# Major_Buzz_Kill.net
KiCad netlist of a schematic drawn in Altium Designer
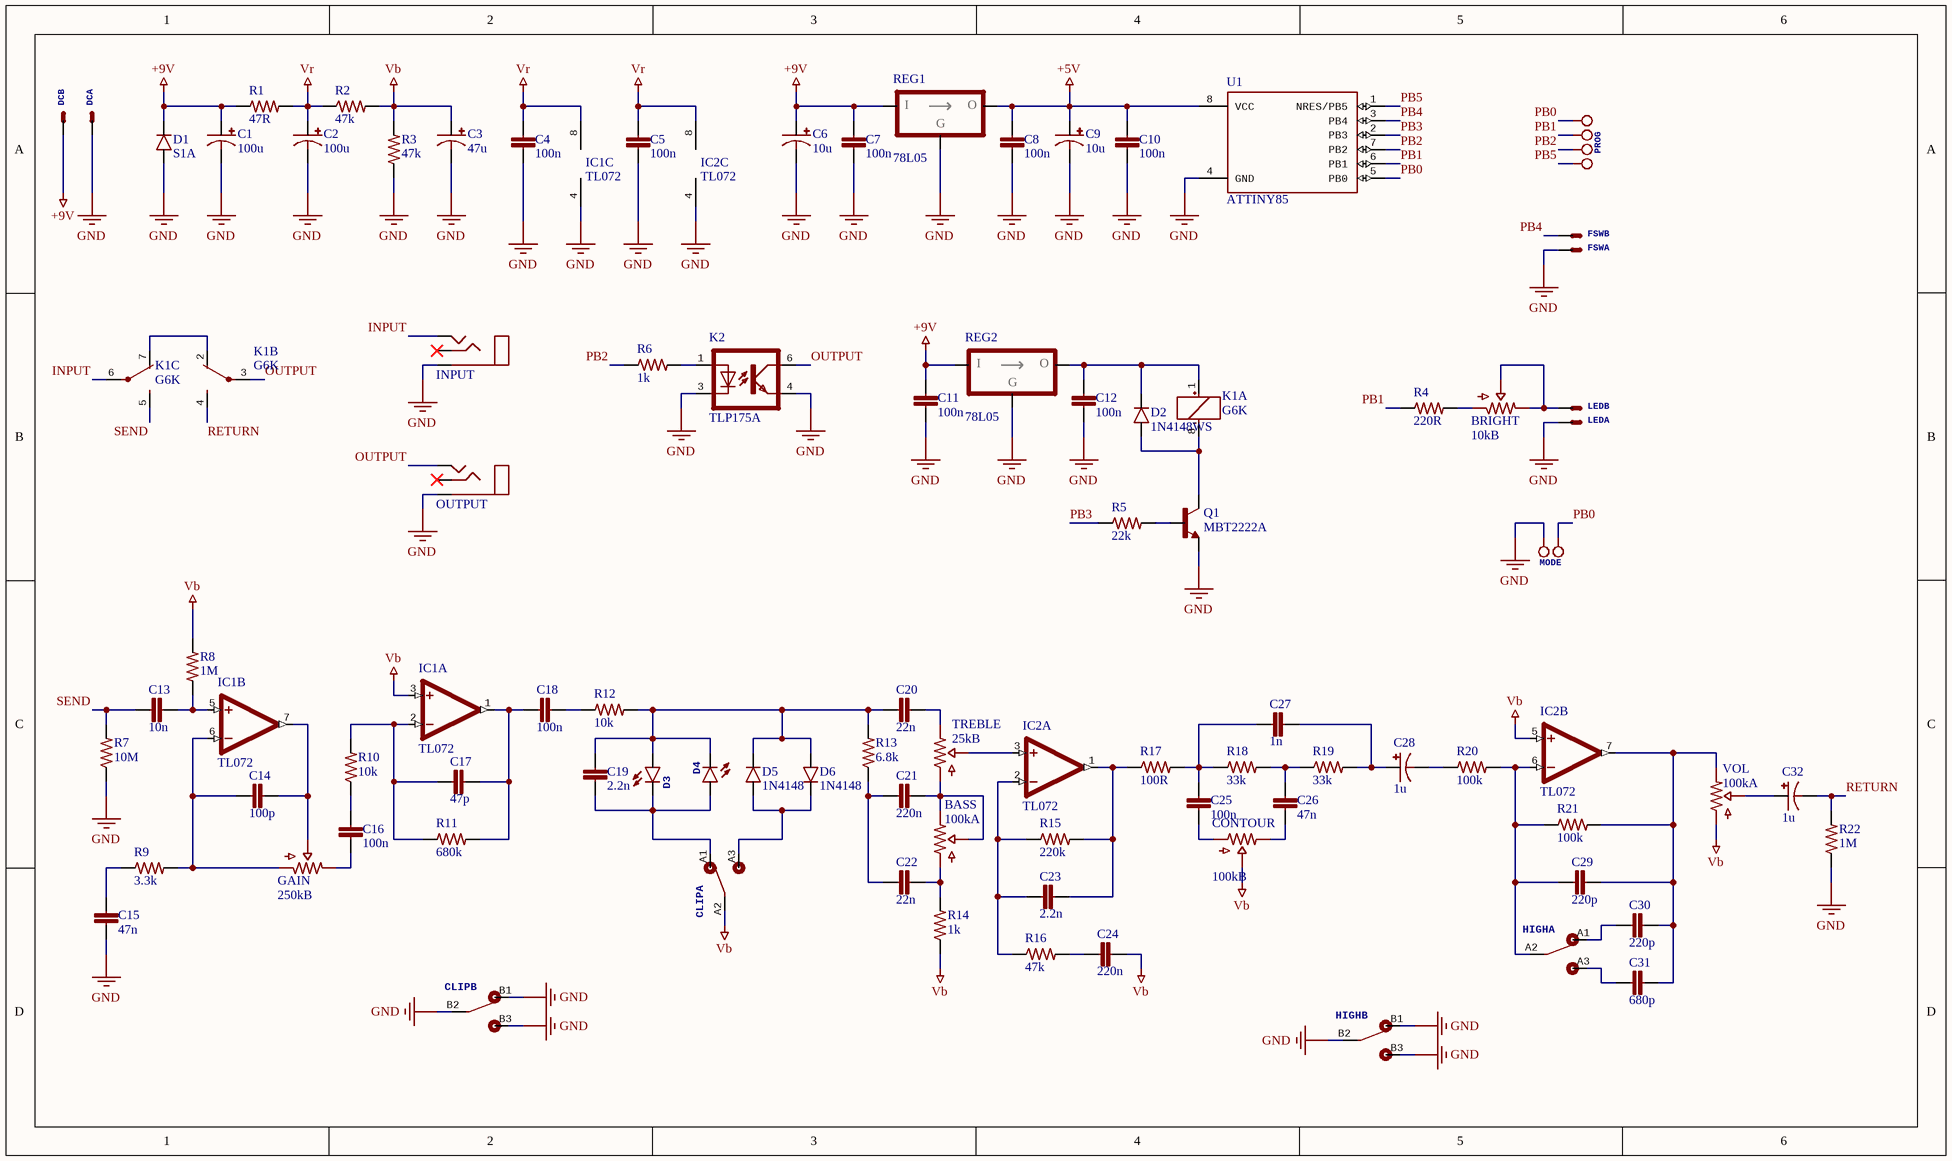
[diagram p0: Major Buzz Kill.SchDoc]

(export (version "E")
  (design (tool "Eeschema 10.0.6"))
  (components
    (comp (ref "BASS")
      (value "100kA")
      (footprint "ALPHA_16mm_BOTTOM")
      (description "100k Log potentiometer round shaft")
      (libsource (lib "Pedals") (part "POT_100kA_ALPHA_16mm"))
    )
    (comp (ref "BRIGHT")
      (value "10kB")
      (footprint "BOURNS_3362P")
      (description "10k Lin 3362P trimmer")
      (libsource (lib "Pedals") (part "TRIM_10kB_3362P"))
    )
    (comp (ref "C1")
      (value "100u")
      (footprint "CAPAE_D")
      (description "CAP ALUM 100UF 25V SMD")
      (fields
        (field (name "MANUFACTURER") "Multicomp")
        (field (name "MANUFACTURER PART NUMBER") "MCVVT025M101EA6L")
      )
      (libsource (lib "Pedals SMD") (part "MCVVT025M101EA6L"))
    )
    (comp (ref "C2")
      (value "100u")
      (footprint "CAPAE_D")
      (description "CAP ALUM 100UF 25V SMD")
      (fields
        (field (name "MANUFACTURER") "Multicomp")
        (field (name "MANUFACTURER PART NUMBER") "MCVVT025M101EA6L")
      )
      (libsource (lib "Pedals SMD") (part "MCVVT025M101EA6L"))
    )
    (comp (ref "C3")
      (value "47u")
      (footprint "CAPAE_D")
      (description "CAP ALUM 47UF 25V SMD")
      (fields
        (field (name "MANUFACTURER") "Multicomp")
        (field (name "MANUFACTURER PART NUMBER") "MCVVT025M470EA1L")
      )
      (libsource (lib "Pedals SMD") (part "MCVVT025M470EA1L"))
    )
    (comp (ref "C4")
      (value "100n")
      (footprint "CHIP_0603")
      (description "CAP CER 100NF 50V X7R 0603")
      (fields
        (field (name "MANUFACTURER") "Multicomp")
        (field (name "MANUFACTURER PART NUMBER") "MC0603B104K500CT")
      )
      (libsource (lib "Pedals SMD") (part "MC0603B104K500CT"))
    )
    (comp (ref "C5")
      (value "100n")
      (footprint "CHIP_0603")
      (description "CAP CER 100NF 50V X7R 0603")
      (fields
        (field (name "MANUFACTURER") "Multicomp")
        (field (name "MANUFACTURER PART NUMBER") "MC0603B104K500CT")
      )
      (libsource (lib "Pedals SMD") (part "MC0603B104K500CT"))
    )
    (comp (ref "C6")
      (value "10u")
      (footprint "CAPAE_B")
      (description "CAP ALUM 10UF 25V SMD")
      (fields
        (field (name "MANUFACTURER") "Multicomp")
        (field (name "MANUFACTURER PART NUMBER") "MCVVT025M100CA1L")
      )
      (libsource (lib "Pedals SMD") (part "MCVVT025M100CA1L"))
    )
    (comp (ref "C7")
      (value "100n")
      (footprint "CHIP_0603")
      (description "CAP CER 100NF 50V X7R 0603")
      (fields
        (field (name "MANUFACTURER") "Multicomp")
        (field (name "MANUFACTURER PART NUMBER") "MC0603B104K500CT")
      )
      (libsource (lib "Pedals SMD") (part "MC0603B104K500CT"))
    )
    (comp (ref "C8")
      (value "100n")
      (footprint "CHIP_0603")
      (description "CAP CER 100NF 50V X7R 0603")
      (fields
        (field (name "MANUFACTURER") "Multicomp")
        (field (name "MANUFACTURER PART NUMBER") "MC0603B104K500CT")
      )
      (libsource (lib "Pedals SMD") (part "MC0603B104K500CT"))
    )
    (comp (ref "C9")
      (value "10u")
      (footprint "CAPAE_B")
      (description "CAP ALUM 10UF 25V SMD")
      (fields
        (field (name "MANUFACTURER") "Multicomp")
        (field (name "MANUFACTURER PART NUMBER") "MCVVT025M100CA1L")
      )
      (libsource (lib "Pedals SMD") (part "MCVVT025M100CA1L"))
    )
    (comp (ref "C10")
      (value "100n")
      (footprint "CHIP_0603")
      (description "CAP CER 100NF 50V X7R 0603")
      (fields
        (field (name "MANUFACTURER") "Multicomp")
        (field (name "MANUFACTURER PART NUMBER") "MC0603B104K500CT")
      )
      (libsource (lib "Pedals SMD") (part "MC0603B104K500CT"))
    )
    (comp (ref "C11")
      (value "100n")
      (footprint "CHIP_0603")
      (description "CAP CER 100NF 50V X7R 0603")
      (fields
        (field (name "MANUFACTURER") "Multicomp")
        (field (name "MANUFACTURER PART NUMBER") "MC0603B104K500CT")
      )
      (libsource (lib "Pedals SMD") (part "MC0603B104K500CT"))
    )
    (comp (ref "C12")
      (value "100n")
      (footprint "CHIP_0603")
      (description "CAP CER 100NF 50V X7R 0603")
      (fields
        (field (name "MANUFACTURER") "Multicomp")
        (field (name "MANUFACTURER PART NUMBER") "MC0603B104K500CT")
      )
      (libsource (lib "Pedals SMD") (part "MC0603B104K500CT"))
    )
    (comp (ref "C13")
      (value "10n")
      (footprint "CHIP_0603")
      (description "CAP CER 10NF 50V C0G/NP0 0603")
      (fields
        (field (name "MANUFACTURER") "Murata")
        (field (name "MANUFACTURER PART NUMBER") "GRM1885C1H103JA01D")
      )
      (libsource (lib "Pedals SMD") (part "GRM1885C1H103JA01D"))
    )
    (comp (ref "C14")
      (value "100p")
      (footprint "CHIP_0603")
      (description "CAP CER 100PF 50V C0G/NP0 0603")
      (fields
        (field (name "MANUFACTURER") "Multicomp")
        (field (name "MANUFACTURER PART NUMBER") "MC0603N101J500CT")
      )
      (libsource (lib "Pedals SMD") (part "MC0603N101J500CT"))
    )
    (comp (ref "C15")
      (value "47n")
      (footprint "CHIP_0603")
      (description "CAP CER 47NF 50V X7R 0603")
      (fields
        (field (name "MANUFACTURER") "Multicomp")
        (field (name "MANUFACTURER PART NUMBER") "MC0603B473K500CT")
      )
      (libsource (lib "Pedals SMD") (part "MC0603B473K500CT"))
    )
    (comp (ref "C16")
      (value "100n")
      (footprint "CHIP_1206")
      (description "CAP CER 100NF 50V C0G/NP0 1206")
      (fields
        (field (name "MANUFACTURER") "Murata")
        (field (name "MANUFACTURER PART NUMBER") "GRM31C5C1H104JA01L")
      )
      (libsource (lib "Pedals SMD") (part "GRM31C5C1H104JA01L"))
    )
    (comp (ref "C17")
      (value "47p")
      (footprint "CHIP_0603")
      (description "CAP CER 47PF 50V C0G/NP0 0603")
      (fields
        (field (name "MANUFACTURER") "Multicomp")
        (field (name "MANUFACTURER PART NUMBER") "MC0603N470J500CT")
      )
      (libsource (lib "Pedals SMD") (part "MC0603N470J500CT"))
    )
    (comp (ref "C18")
      (value "100n")
      (footprint "CHIP_1206")
      (description "CAP CER 100NF 50V C0G/NP0 1206")
      (fields
        (field (name "MANUFACTURER") "Murata")
        (field (name "MANUFACTURER PART NUMBER") "GRM31C5C1H104JA01L")
      )
      (libsource (lib "") (part "GRM31C5C1H104JA01L_1"))
    )
    (comp (ref "C19")
      (value "2.2n")
      (footprint "CHIP_0603")
      (description "CAP CER 2.2NF 50V C0G/NP0 0603")
      (fields
        (field (name "MANUFACTURER") "Murata")
        (field (name "MANUFACTURER PART NUMBER") "GRM1885C1H222JA01D")
      )
      (libsource (lib "Pedals SMD") (part "GRM1885C1H222JA01D"))
    )
    (comp (ref "C20")
      (value "22n")
      (footprint "CHIP_0805")
      (description "CAP CER 22NF 50V C0G/NP0 0805")
      (fields
        (field (name "MANUFACTURER") "Murata")
        (field (name "MANUFACTURER PART NUMBER") "GRM21B5C1H223JA01L")
      )
      (libsource (lib "Pedals SMD") (part "GRM21B5C1H223JA01L"))
    )
    (comp (ref "C21")
      (value "220n")
      (footprint "CHIP_0603")
      (description "CAP CER 220n 50V X7R 0603")
      (fields
        (field (name "MANUFACTURER") "Murata")
        (field (name "MANUFACTURER PART NUMBER") "GCM188R71H224KA64D")
      )
      (libsource (lib "Pedals SMD") (part "GCM188R71H224KA64D"))
    )
    (comp (ref "C22")
      (value "22n")
      (footprint "CHIP_0805")
      (description "CAP CER 22NF 50V C0G/NP0 0805")
      (fields
        (field (name "MANUFACTURER") "Murata")
        (field (name "MANUFACTURER PART NUMBER") "GRM21B5C1H223JA01L")
      )
      (libsource (lib "Pedals SMD") (part "GRM21B5C1H223JA01L"))
    )
    (comp (ref "C23")
      (value "2.2n")
      (footprint "CHIP_0603")
      (description "CAP CER 2.2NF 50V C0G/NP0 0603")
      (fields
        (field (name "MANUFACTURER") "Murata")
        (field (name "MANUFACTURER PART NUMBER") "GRM1885C1H222JA01D")
      )
      (libsource (lib "") (part "GRM1885C1H222JA01D_1"))
    )
    (comp (ref "C24")
      (value "220n")
      (footprint "CHIP_0603")
      (description "CAP CER 220n 50V X7R 0603")
      (fields
        (field (name "MANUFACTURER") "Murata")
        (field (name "MANUFACTURER PART NUMBER") "GCM188R71H224KA64D")
      )
      (libsource (lib "Pedals SMD") (part "GCM188R71H224KA64D"))
    )
    (comp (ref "C25")
      (value "100n")
      (footprint "CHIP_1206")
      (description "CAP CER 100NF 50V C0G/NP0 1206")
      (fields
        (field (name "MANUFACTURER") "Murata")
        (field (name "MANUFACTURER PART NUMBER") "GRM31C5C1H104JA01L")
      )
      (libsource (lib "Pedals SMD") (part "GRM31C5C1H104JA01L"))
    )
    (comp (ref "C26")
      (value "47n")
      (footprint "CHIP_1206")
      (description "CAP CER 47NF 50V C0G/NP0 1206")
      (fields
        (field (name "MANUFACTURER") "Murata")
        (field (name "MANUFACTURER PART NUMBER") "GCM31M5C1H473JA16L")
      )
      (libsource (lib "Pedals SMD") (part "GCM31M5C1H473JA16L"))
    )
    (comp (ref "C27")
      (value "1n")
      (footprint "CHIP_0603")
      (description "CAP CER 1NF 50V C0G/NP0 0603")
      (fields
        (field (name "MANUFACTURER") "Murata")
        (field (name "MANUFACTURER PART NUMBER") "GRM1885C1H102JA01D")
      )
      (libsource (lib "Pedals SMD") (part "GRM1885C1H102JA01D"))
    )
    (comp (ref "C28")
      (value "1u")
      (footprint "CAPAE_B")
      (description "CAP ALUM 1UF 50V LESR SMD")
      (fields
        (field (name "MANUFACTURER") "Panasonic")
        (field (name "MANUFACTURER PART NUMBER") "EEEFC1H1R0R")
      )
      (libsource (lib "Pedals SMD") (part "EEEFC1H1R0R"))
    )
    (comp (ref "C29")
      (value "220p")
      (footprint "CHIP_0603")
      (description "CAP CER 220PF 50V C0G/NP0 0603")
      (fields
        (field (name "MANUFACTURER") "Multicomp")
        (field (name "MANUFACTURER PART NUMBER") "MC0603N221J500CT")
      )
      (libsource (lib "Pedals SMD") (part "MC0603N221J500CT"))
    )
    (comp (ref "C30")
      (value "220p")
      (footprint "CHIP_0603")
      (description "CAP CER 220PF 50V C0G/NP0 0603")
      (fields
        (field (name "MANUFACTURER") "Multicomp")
        (field (name "MANUFACTURER PART NUMBER") "MC0603N221J500CT")
      )
      (libsource (lib "Pedals SMD") (part "MC0603N221J500CT"))
    )
    (comp (ref "C31")
      (value "680p")
      (footprint "CHIP_0603")
      (description "CAP CER 680PF 50V C0G/NP0 0603")
      (fields
        (field (name "MANUFACTURER") "Multicomp")
        (field (name "MANUFACTURER PART NUMBER") "MC0603N681J500CT")
      )
      (libsource (lib "Pedals SMD") (part "MC0603N681J500CT"))
    )
    (comp (ref "C32")
      (value "1u")
      (footprint "CAPAE_B")
      (description "CAP ALUM 1UF 50V LESR SMD")
      (fields
        (field (name "MANUFACTURER") "Panasonic")
        (field (name "MANUFACTURER PART NUMBER") "EEEFC1H1R0R")
      )
      (libsource (lib "Pedals SMD") (part "EEEFC1H1R0R"))
    )
    (comp (ref "CLIP")
      (value "DPDT")
      (footprint "DPDT_SLIDE")
      (description "DPDT slide switch ON/OFF/ON")
      (libsource (lib "") (part "SW_SLIDE_DPDT_ON-OFF-ON_1"))
    )
    (comp (ref "CONTOUR")
      (value "100kB")
      (footprint "ALPHA_16mm_BOTTOM")
      (description "100k Lin potentiometer round shaft")
      (libsource (lib "Pedals") (part "POT_100kB_ALPHA_16mm"))
    )
    (comp (ref "D1")
      (value "S1A")
      (footprint "DO214")
      (description "DIODE GEN PURP 50V 1A SMA")
      (fields (field (name "MANUFACTURER") "ON Semiconductor / Fairchild"))
      (libsource (lib "Pedals SMD") (part "S1A"))
    )
    (comp (ref "D2")
      (value "1N4148WS")
      (footprint "SOD323")
      (description "DIODE GEN PURP 75V 150MA SOD323F")
      (fields (field (name "MANUFACTURER") "ON Semiconductor / Fairchild"))
      (libsource (lib "Pedals SMD") (part "1N4148WS"))
    )
    (comp (ref "D3")
      (value "D_LED")
      (footprint "LED_3MM")
      (description "LED")
      (libsource (lib "Pedals") (part "D_LED"))
    )
    (comp (ref "D4")
      (value "D_LED")
      (footprint "LED_3MM")
      (description "LED")
      (libsource (lib "Pedals") (part "D_LED"))
    )
    (comp (ref "D5") (value "1N4148") (footprint "DO35_2") (libsource (lib "Pedals") (part "D_1N4148")))
    (comp (ref "D6") (value "1N4148") (footprint "DO35_2") (libsource (lib "Pedals") (part "D_1N4148")))
    (comp (ref "DC")
      (value "J_JST-XH-02")
      (footprint "JST-XH-02")
      (description "2 Pins male XH header")
      (libsource (lib "Pedals") (part "J_JST-XH-02"))
    )
    (comp (ref "FSW")
      (value "J_JST-XH-02")
      (footprint "JST-XH-02")
      (description "2 Pins male XH header")
      (libsource (lib "Pedals") (part "J_JST-XH-02"))
    )
    (comp (ref "GAIN")
      (value "250kB")
      (footprint "ALPHA_16mm_BOTTOM")
      (description "250k Lin potentiometer round shaft")
      (libsource (lib "Pedals") (part "POT_250kB_ALPHA_16mm"))
    )
    (comp (ref "HIGH")
      (value "DPDT")
      (footprint "DPDT_SLIDE")
      (description "DPDT slide switch ON/OFF/ON")
      (libsource (lib "") (part "SW_SLIDE_DPDT_ON-OFF-ON_2"))
    )
    (comp (ref "IC1")
      (value "TL072")
      (footprint "SO-8")
      (description "IC OPAMP JFET 4MHZ 8SO")
      (fields
        (field (name "MANUFACTURER") "STMicroelectronics")
        (field (name "MANUFACTURER PART NUMBER") "TL072CDT")
      )
      (libsource (lib "Pedals SMD") (part "TL072CDT"))
    )
    (comp (ref "IC2")
      (value "TL072")
      (footprint "SO-8")
      (description "IC OPAMP JFET 4MHZ 8SO")
      (fields
        (field (name "MANUFACTURER") "STMicroelectronics")
        (field (name "MANUFACTURER PART NUMBER") "TL072CDT")
      )
      (libsource (lib "Pedals SMD") (part "TL072CDT"))
    )
    (comp (ref "INPUT")
      (value "J_STEREO")
      (footprint "STEREO")
      (description "6.35mm stereo insulated socket jack PCB mounted")
      (libsource (lib "Pedals") (part "J_STEREO"))
    )
    (comp (ref "K1")
      (value "G6K")
      (footprint "G6K")
      (description "OMRON - G6K-2F 5DC - RELAY, SIGNAL, DPDT, 30VDC, 1A")
      (fields (field (name "MANUFACTURER") "Cliff") (field (name "MANUFACTURER PART NUMBER") "G6K-2F5DC"))
      (libsource (lib "") (part "G6K-2F5DC_1"))
    )
    (comp (ref "K2")
      (value "TLP175A")
      (footprint "TLP175A")
      (description "Toshiba TLP175A AC Input MOSFET Output Optocoupler, Surface Mount, 4-Pin SOIC")
      (fields (field (name "MANUFACTURER") "Toshiba"))
      (libsource (lib "Pedals SMD") (part "TLP175A"))
    )
    (comp (ref "LED")
      (value "J_JST-XH-02")
      (footprint "JST-XH-02")
      (description "2 Pins male XH header")
      (libsource (lib "Pedals") (part "J_JST-XH-02"))
    )
    (comp (ref "MODE")
      (value "J_HEADER_2PINS")
      (footprint "HEADER_2PINS")
      (description "2 Pins male header")
      (libsource (lib "Pedals") (part "J_HEADER_2PINS"))
    )
    (comp (ref "OUTPUT")
      (value "J_STEREO")
      (footprint "STEREO")
      (description "6.35mm stereo insulated socket jack PCB mounted")
      (libsource (lib "Pedals") (part "J_STEREO"))
    )
    (comp (ref "PROG")
      (value "J_HEADER_4PINS_FEM")
      (footprint "HEADER_4Pins_FEM")
      (description "4 Pins female header")
      (libsource (lib "Pedals") (part "J_HEADER_4PINS_FEM"))
    )
    (comp (ref "Q1")
      (value "MBT2222A")
      (footprint "SOT323")
      (description "TRANS NPN 40V 0.6A SOT323")
      (fields
        (field (name "MANUFACTURER") "ON Semiconductor")
        (field (name "MANUFACTURER PART NUMBER") "MMBT2222AWT1G")
      )
      (libsource (lib "Pedals SMD") (part "MMBT2222AWT1G"))
    )
    (comp (ref "R1")
      (value "47R")
      (footprint "CHIP_R_1206")
      (description "RES SMD 47 OHM 1% 1/4W 1206")
      (fields
        (field (name "MANUFACTURER") "Vishay")
        (field (name "MANUFACTURER PART NUMBER") "CRCW120647R0FKEA")
      )
      (libsource (lib "Pedals SMD") (part "CRCW120647R0FKEA"))
    )
    (comp (ref "R2")
      (value "47k")
      (footprint "CHIP_R_1206")
      (description "RES SMD 47K OHM 1% 1/4W 1206")
      (fields
        (field (name "MANUFACTURER") "Vishay")
        (field (name "MANUFACTURER PART NUMBER") "CRCW120647K0FKEA")
      )
      (libsource (lib "Pedals SMD") (part "CRCW120647K0FKEA"))
    )
    (comp (ref "R3")
      (value "47k")
      (footprint "CHIP_R_1206")
      (description "RES SMD 47K OHM 1% 1/4W 1206")
      (fields
        (field (name "MANUFACTURER") "Vishay")
        (field (name "MANUFACTURER PART NUMBER") "CRCW120647K0FKEA")
      )
      (libsource (lib "Pedals SMD") (part "CRCW120647K0FKEA"))
    )
    (comp (ref "R4")
      (value "220R")
      (footprint "CHIP_R_1206")
      (description "RES SMD 220 OHM 1% 1/4W 1206")
      (fields
        (field (name "MANUFACTURER") "Vishay")
        (field (name "MANUFACTURER PART NUMBER") "CRCW1206220RFKEA")
      )
      (libsource (lib "Pedals SMD") (part "CRCW1206220RFKEA"))
    )
    (comp (ref "R5")
      (value "22k")
      (footprint "CHIP_R_0603")
      (description "RES SMD 22K OHM 1% 1/10W 0603")
      (fields
        (field (name "MANUFACTURER") "Vishay")
        (field (name "MANUFACTURER PART NUMBER") "CRCW060322K0FKEA")
      )
      (libsource (lib "Pedals SMD") (part "CRCW060322K0FKEA"))
    )
    (comp (ref "R6")
      (value "1k")
      (footprint "CHIP_R_0603")
      (description "RES SMD 1K OHM 1% 1/10W 0603")
      (fields
        (field (name "MANUFACTURER") "Vishay Dale")
        (field (name "MANUFACTURER PART NUMBER") "CRCW06031K00FKEA")
      )
      (libsource (lib "Pedals SMD") (part "CRCW06031K00FKEA"))
    )
    (comp (ref "R7")
      (value "10M")
      (footprint "CHIP_R_0603")
      (description "RES SMD 10M OHM 1% 1/10W 0603")
      (fields
        (field (name "MANUFACTURER") "Vishay")
        (field (name "MANUFACTURER PART NUMBER") "CRCW060310M0FKEA")
      )
      (libsource (lib "Pedals SMD") (part "CRCW060310M0FKEA"))
    )
    (comp (ref "R8")
      (value "1M")
      (footprint "CHIP_R_0603")
      (description "RES SMD 1M OHM 1% 1/10W 0603")
      (fields
        (field (name "MANUFACTURER") "Vishay")
        (field (name "MANUFACTURER PART NUMBER") "CRCW06031M00FKEA")
      )
      (libsource (lib "Pedals SMD") (part "CRCW06031M00FKEA"))
    )
    (comp (ref "R9")
      (value "3.3k")
      (footprint "CHIP_R_0603")
      (description "RES SMD 3.3K OHM 1% 1/10W 0603")
      (fields
        (field (name "MANUFACTURER") "Vishay")
        (field (name "MANUFACTURER PART NUMBER") "CRCW06033K30FKEA")
      )
      (libsource (lib "Pedals SMD") (part "CRCW06033K30FKEA"))
    )
    (comp (ref "R10")
      (value "10k")
      (footprint "CHIP_R_0603")
      (description "RES SMD 10K OHM 1% 1/10W 0603")
      (fields
        (field (name "MANUFACTURER") "Vishay")
        (field (name "MANUFACTURER PART NUMBER") "CRCW060310K0FKEA")
      )
      (libsource (lib "Pedals SMD") (part "CRCW060310K0FKEA"))
    )
    (comp (ref "R11")
      (value "680k")
      (footprint "CHIP_R_0603")
      (description "RES SMD 680K OHM 1% 1/10W 0603")
      (fields
        (field (name "MANUFACTURER") "Vishay")
        (field (name "MANUFACTURER PART NUMBER") "CRCW0603680KFKEA")
      )
      (libsource (lib "Pedals SMD") (part "CRCW0603680KFKEA"))
    )
    (comp (ref "R12")
      (value "10k")
      (footprint "CHIP_R_0603")
      (description "RES SMD 10K OHM 1% 1/10W 0603")
      (fields
        (field (name "MANUFACTURER") "Vishay")
        (field (name "MANUFACTURER PART NUMBER") "CRCW060310K0FKEA")
      )
      (libsource (lib "Pedals SMD") (part "CRCW060310K0FKEA"))
    )
    (comp (ref "R13")
      (value "6.8k")
      (footprint "CHIP_R_0603")
      (description "RES SMD 6.8K OHM 1% 1/10W 0603")
      (fields
        (field (name "MANUFACTURER") "Vishay")
        (field (name "MANUFACTURER PART NUMBER") "CRCW06036K80FKEA")
      )
      (libsource (lib "Pedals SMD") (part "CRCW06036K80FKEA"))
    )
    (comp (ref "R14")
      (value "1k")
      (footprint "CHIP_R_0603")
      (description "RES SMD 1K OHM 1% 1/10W 0603")
      (fields
        (field (name "MANUFACTURER") "Vishay Dale")
        (field (name "MANUFACTURER PART NUMBER") "CRCW06031K00FKEA")
      )
      (libsource (lib "Pedals SMD") (part "CRCW06031K00FKEA"))
    )
    (comp (ref "R15")
      (value "220k")
      (footprint "CHIP_R_0603")
      (description "RES SMD 220K OHM 1% 1/10W 0603")
      (fields
        (field (name "MANUFACTURER") "Vishay")
        (field (name "MANUFACTURER PART NUMBER") "CRCW0603220KFKEA")
      )
      (libsource (lib "Pedals SMD") (part "CRCW0603220KFKEA"))
    )
    (comp (ref "R16")
      (value "47k")
      (footprint "CHIP_R_0603")
      (description "RES SMD 47K OHM 1% 1/10W 0603")
      (fields
        (field (name "MANUFACTURER") "Vishay")
        (field (name "MANUFACTURER PART NUMBER") "CRCW060347K0FKEA")
      )
      (libsource (lib "Pedals SMD") (part "CRCW060347K0FKEA"))
    )
    (comp (ref "R17")
      (value "100R")
      (footprint "CHIP_R_0603")
      (description "RES SMD 100 OHM 1% 1/10W 0603")
      (fields
        (field (name "MANUFACTURER") "Vishay Dale")
        (field (name "MANUFACTURER PART NUMBER") "CRCW0603100RFKEA")
      )
      (libsource (lib "Pedals SMD") (part "CRCW0603100RFKEA"))
    )
    (comp (ref "R18")
      (value "33k")
      (footprint "CHIP_R_0603")
      (description "RES SMD 33K OHM 1% 1/10W 0603")
      (fields
        (field (name "MANUFACTURER") "Vishay")
        (field (name "MANUFACTURER PART NUMBER") "CRCW060333K0FKEA")
      )
      (libsource (lib "Pedals SMD") (part "CRCW060333K0FKEA"))
    )
    (comp (ref "R19")
      (value "33k")
      (footprint "CHIP_R_0603")
      (description "RES SMD 33K OHM 1% 1/10W 0603")
      (fields
        (field (name "MANUFACTURER") "Vishay")
        (field (name "MANUFACTURER PART NUMBER") "CRCW060333K0FKEA")
      )
      (libsource (lib "Pedals SMD") (part "CRCW060333K0FKEA"))
    )
    (comp (ref "R20")
      (value "100k")
      (footprint "CHIP_R_0603")
      (description "RES SMD 100K OHM 1% 1/10W 0603")
      (fields
        (field (name "MANUFACTURER") "Vishay")
        (field (name "MANUFACTURER PART NUMBER") "CRCW0603100KFKEA")
      )
      (libsource (lib "Pedals SMD") (part "CRCW0603100KFKEA"))
    )
    (comp (ref "R21")
      (value "100k")
      (footprint "CHIP_R_0603")
      (description "RES SMD 100K OHM 1% 1/10W 0603")
      (fields
        (field (name "MANUFACTURER") "Vishay")
        (field (name "MANUFACTURER PART NUMBER") "CRCW0603100KFKEA")
      )
      (libsource (lib "Pedals SMD") (part "CRCW0603100KFKEA"))
    )
    (comp (ref "R22")
      (value "1M")
      (footprint "CHIP_R_0603")
      (description "RES SMD 1M OHM 1% 1/10W 0603")
      (fields
        (field (name "MANUFACTURER") "Vishay")
        (field (name "MANUFACTURER PART NUMBER") "CRCW06031M00FKEA")
      )
      (libsource (lib "Pedals SMD") (part "CRCW06031M00FKEA"))
    )
    (comp (ref "REG1")
      (value "78L05")
      (footprint "SOT23-3")
      (description "TAIWAN SEMICONDUCTOR - TS78L05CX RFG - REG 3-TERMINAL 100MA, SMD, SOT23-3")
      (fields
        (field (name "MANUFACTURER") "Taiwan Semiconductor")
        (field (name "MANUFACTURER PART NUMBER") "TS78L05CXRFG")
      )
      (libsource (lib "Pedals SMD") (part "TS78L05CXRFG"))
    )
    (comp (ref "REG2")
      (value "78L05")
      (footprint "SOT23-3")
      (description "TAIWAN SEMICONDUCTOR - TS78L05CX RFG - REG 3-TERMINAL 100MA, SMD, SOT23-3")
      (fields
        (field (name "MANUFACTURER") "Taiwan Semiconductor")
        (field (name "MANUFACTURER PART NUMBER") "TS78L05CXRFG")
      )
      (libsource (lib "Pedals SMD") (part "TS78L05CXRFG"))
    )
    (comp (ref "TREBLE")
      (value "25kB")
      (footprint "ALPHA_16mm_BOTTOM")
      (description "25k Lin potentiometer round shaft")
      (libsource (lib "Pedals") (part "POT_25kB_ALPHA_16mm"))
    )
    (comp (ref "U1")
      (value "ATTINY85")
      (footprint "SOP8")
      (description "IC, 8BIT MCU, AVR TINY, 20MHZ, 8-SOIC")
      (fields
        (field (name "MANUFACTURER") "Microchip / Atmel")
        (field (name "MANUFACTURER PART NUMBER") "ATTINY85-20SU")
      )
      (libsource (lib "Pedals SMD") (part "ATTINY85-20SU"))
    )
    (comp (ref "VOL")
      (value "100kA")
      (footprint "ALPHA_16mm_BOTTOM")
      (description "100k Log potentiometer round shaft")
      (libsource (lib "Pedals") (part "POT_100kA_ALPHA_16mm"))
    )
  )
  (nets
    (net (code "1") (name "+5V") (class "Default")
      (node (ref "C10") (pin "1") (pinfunction "1_1") (pintype "passive"))
      (node (ref "C8") (pin "1") (pinfunction "1_1") (pintype "passive"))
      (node (ref "C9") (pin "+") (pinfunction "+_+") (pintype "passive"))
      (node (ref "REG1") (pin "1") (pinfunction "OUTPUT_1") (pintype "power_in"))
      (node (ref "U1") (pin "8") (pinfunction "VCC_8") (pintype "power_in"))
    )
    (net (code "2") (name "+9V") (class "Default")
      (node (ref "C1") (pin "+") (pinfunction "+_+") (pintype "passive"))
      (node (ref "C11") (pin "1") (pinfunction "1_1") (pintype "passive"))
      (node (ref "C6") (pin "+") (pinfunction "+_+") (pintype "passive"))
      (node (ref "C7") (pin "1") (pinfunction "1_1") (pintype "passive"))
      (node (ref "D1") (pin "1") (pinfunction "1_1") (pintype "passive"))
      (node (ref "DC") (pin "1") (pinfunction "S_1") (pintype "passive"))
      (node (ref "R1") (pin "1") (pinfunction "1_1") (pintype "passive"))
      (node (ref "REG1") (pin "2") (pinfunction "INPUT_2") (pintype "power_in"))
      (node (ref "REG2") (pin "2") (pinfunction "INPUT_2") (pintype "power_in"))
    )
    (net (code "3") (name "/INPUT") (class "Default")
      (node (ref "INPUT") (pin "T") (pinfunction "T_T") (pintype "passive"))
      (node (ref "K1") (pin "6") (pinfunction "P_6") (pintype "passive"))
    )
    (net (code "4") (name "/OUTPUT") (class "Default")
      (node (ref "K1") (pin "3") (pinfunction "P_3") (pintype "passive"))
      (node (ref "K2") (pin "6") (pinfunction "COL_6") (pintype "passive"))
      (node (ref "OUTPUT") (pin "T") (pinfunction "T_T") (pintype "passive"))
    )
    (net (code "5") (name "/PB0") (class "Default")
      (node (ref "MODE") (pin "2") (pinfunction "2_2") (pintype "passive"))
      (node (ref "PROG") (pin "4") (pinfunction "4_4") (pintype "passive"))
      (node (ref "U1") (pin "5") (pinfunction "PB0_5") (pintype "bidirectional"))
    )
    (net (code "6") (name "/PB1") (class "Default")
      (node (ref "PROG") (pin "3") (pinfunction "3_3") (pintype "passive"))
      (node (ref "R4") (pin "1") (pinfunction "1_1") (pintype "passive"))
      (node (ref "U1") (pin "6") (pinfunction "PB1_6") (pintype "bidirectional"))
    )
    (net (code "7") (name "/PB2") (class "Default")
      (node (ref "PROG") (pin "2") (pinfunction "2_2") (pintype "passive"))
      (node (ref "R6") (pin "1") (pinfunction "1_1") (pintype "passive"))
      (node (ref "U1") (pin "7") (pinfunction "PB2_7") (pintype "bidirectional"))
    )
    (net (code "8") (name "/PB3") (class "Default")
      (node (ref "R5") (pin "1") (pinfunction "1_1") (pintype "passive"))
      (node (ref "U1") (pin "2") (pinfunction "PB3_2") (pintype "bidirectional"))
    )
    (net (code "9") (name "/PB4") (class "Default")
      (node (ref "FSW") (pin "1") (pinfunction "S_1") (pintype "passive"))
      (node (ref "U1") (pin "3") (pinfunction "PB4_3") (pintype "bidirectional"))
    )
    (net (code "10") (name "/PB5") (class "Default")
      (node (ref "PROG") (pin "1") (pinfunction "1_1") (pintype "passive"))
      (node (ref "U1") (pin "1") (pinfunction "NRES/PB5_1") (pintype "bidirectional"))
    )
    (net (code "11") (name "/RETURN") (class "Default")
      (node (ref "C32") (pin "-") (pinfunction "-_-") (pintype "passive"))
      (node (ref "K1") (pin "4") (pinfunction "S_4") (pintype "passive"))
      (node (ref "R22") (pin "2") (pinfunction "2_2") (pintype "passive"))
    )
    (net (code "12") (name "/SEND") (class "Default")
      (node (ref "C13") (pin "2") (pinfunction "2_2") (pintype "passive"))
      (node (ref "K1") (pin "5") (pinfunction "S_5") (pintype "passive"))
      (node (ref "R7") (pin "2") (pinfunction "2_2") (pintype "passive"))
    )
    (net (code "13") (name "GND") (class "Default")
      (node (ref "C1") (pin "-") (pinfunction "-_-") (pintype "passive"))
      (node (ref "C10") (pin "2") (pinfunction "2_2") (pintype "passive"))
      (node (ref "C11") (pin "2") (pinfunction "2_2") (pintype "passive"))
      (node (ref "C12") (pin "2") (pinfunction "2_2") (pintype "passive"))
      (node (ref "C15") (pin "2") (pinfunction "2_2") (pintype "passive"))
      (node (ref "C2") (pin "-") (pinfunction "-_-") (pintype "passive"))
      (node (ref "C3") (pin "-") (pinfunction "-_-") (pintype "passive"))
      (node (ref "C4") (pin "2") (pinfunction "2_2") (pintype "passive"))
      (node (ref "C5") (pin "2") (pinfunction "2_2") (pintype "passive"))
      (node (ref "C6") (pin "-") (pinfunction "-_-") (pintype "passive"))
      (node (ref "C7") (pin "2") (pinfunction "2_2") (pintype "passive"))
      (node (ref "C8") (pin "2") (pinfunction "2_2") (pintype "passive"))
      (node (ref "C9") (pin "-") (pinfunction "-_-") (pintype "passive"))
      (node (ref "CLIP") (pin "B1") (pinfunction "1_B1") (pintype "passive"))
      (node (ref "CLIP") (pin "B2") (pinfunction "2_B2") (pintype "passive"))
      (node (ref "CLIP") (pin "B3") (pinfunction "3_B3") (pintype "passive"))
      (node (ref "D1") (pin "2") (pinfunction "2_2") (pintype "passive"))
      (node (ref "DC") (pin "2") (pinfunction "S_2") (pintype "passive"))
      (node (ref "FSW") (pin "2") (pinfunction "S_2") (pintype "passive"))
      (node (ref "HIGH") (pin "B1") (pinfunction "1_B1") (pintype "passive"))
      (node (ref "HIGH") (pin "B2") (pinfunction "2_B2") (pintype "passive"))
      (node (ref "HIGH") (pin "B3") (pinfunction "3_B3") (pintype "passive"))
      (node (ref "IC1") (pin "4") (pinfunction "V-_4") (pintype "power_in"))
      (node (ref "IC2") (pin "4") (pinfunction "V-_4") (pintype "power_in"))
      (node (ref "INPUT") (pin "S") (pinfunction "S_S") (pintype "passive"))
      (node (ref "K2") (pin "3") (pinfunction "C_3") (pintype "passive"))
      (node (ref "K2") (pin "4") (pinfunction "EMIT_4") (pintype "passive"))
      (node (ref "LED") (pin "2") (pinfunction "S_2") (pintype "passive"))
      (node (ref "MODE") (pin "1") (pinfunction "1_1") (pintype "passive"))
      (node (ref "OUTPUT") (pin "S") (pinfunction "S_S") (pintype "passive"))
      (node (ref "Q1") (pin "2") (pinfunction "E_2") (pintype "passive"))
      (node (ref "R22") (pin "1") (pinfunction "1_1") (pintype "passive"))
      (node (ref "R3") (pin "1") (pinfunction "1_1") (pintype "passive"))
      (node (ref "R7") (pin "1") (pinfunction "1_1") (pintype "passive"))
      (node (ref "REG1") (pin "3") (pinfunction "COMMON_3") (pintype "power_in"))
      (node (ref "REG2") (pin "3") (pinfunction "COMMON_3") (pintype "power_in"))
      (node (ref "U1") (pin "4") (pinfunction "GND_4") (pintype "power_in"))
    )
    (net (code "14") (name "Net-(BASS-Pad1)") (class "Default")
      (node (ref "BASS") (pin "1") (pinfunction "1_1") (pintype "passive"))
      (node (ref "C22") (pin "1") (pinfunction "1_1") (pintype "passive"))
      (node (ref "R14") (pin "2") (pinfunction "2_2") (pintype "passive"))
    )
    (net (code "15") (name "Net-(BASS-Pad2)") (class "Default")
      (node (ref "BASS") (pin "2") (pinfunction "2_2") (pintype "passive"))
      (node (ref "BASS") (pin "3") (pinfunction "3_3") (pintype "passive"))
      (node (ref "C21") (pin "1") (pinfunction "1_1") (pintype "passive"))
      (node (ref "TREBLE") (pin "1") (pinfunction "1_1") (pintype "passive"))
    )
    (net (code "16") (name "Net-(BRIGHT-Pad1)") (class "Default")
      (node (ref "BRIGHT") (pin "1") (pinfunction "1_1") (pintype "passive"))
      (node (ref "R4") (pin "2") (pinfunction "2_2") (pintype "passive"))
    )
    (net (code "17") (name "Net-(C15-Pad1)") (class "Default")
      (node (ref "C15") (pin "1") (pinfunction "1_1") (pintype "passive"))
      (node (ref "R9") (pin "1") (pinfunction "1_1") (pintype "passive"))
    )
    (net (code "18") (name "Net-(C16-Pad1)") (class "Default")
      (node (ref "C16") (pin "1") (pinfunction "1_1") (pintype "passive"))
      (node (ref "R10") (pin "1") (pinfunction "1_1") (pintype "passive"))
    )
    (net (code "19") (name "Net-(C16-Pad2)") (class "Default")
      (node (ref "C16") (pin "2") (pinfunction "2_2") (pintype "passive"))
      (node (ref "GAIN") (pin "3") (pinfunction "3_3") (pintype "passive"))
    )
    (net (code "20") (name "Net-(C18-Pad1)") (class "Default")
      (node (ref "C18") (pin "1") (pinfunction "1_1") (pintype "passive"))
      (node (ref "R12") (pin "1") (pinfunction "1_1") (pintype "passive"))
    )
    (net (code "21") (name "Net-(C20-Pad1)") (class "Default")
      (node (ref "C20") (pin "1") (pinfunction "1_1") (pintype "passive"))
      (node (ref "TREBLE") (pin "3") (pinfunction "3_3") (pintype "passive"))
    )
    (net (code "22") (name "Net-(C21-Pad2)") (class "Default")
      (node (ref "C21") (pin "2") (pinfunction "2_2") (pintype "passive"))
      (node (ref "C22") (pin "2") (pinfunction "2_2") (pintype "passive"))
      (node (ref "R13") (pin "1") (pinfunction "1_1") (pintype "passive"))
    )
    (net (code "23") (name "Net-(C24-Pad2)") (class "Default")
      (node (ref "C24") (pin "2") (pinfunction "2_2") (pintype "passive"))
      (node (ref "R16") (pin "2") (pinfunction "2_2") (pintype "passive"))
    )
    (net (code "24") (name "Net-(C25-Pad1)") (class "Default")
      (node (ref "C25") (pin "1") (pinfunction "1_1") (pintype "passive"))
      (node (ref "C27") (pin "2") (pinfunction "2_2") (pintype "passive"))
      (node (ref "R17") (pin "2") (pinfunction "2_2") (pintype "passive"))
      (node (ref "R18") (pin "1") (pinfunction "1_1") (pintype "passive"))
    )
    (net (code "25") (name "Net-(C25-Pad2)") (class "Default")
      (node (ref "C25") (pin "2") (pinfunction "2_2") (pintype "passive"))
      (node (ref "CONTOUR") (pin "1") (pinfunction "1_1") (pintype "passive"))
    )
    (net (code "26") (name "Net-(C26-Pad1)") (class "Default")
      (node (ref "C26") (pin "1") (pinfunction "1_1") (pintype "passive"))
      (node (ref "R18") (pin "2") (pinfunction "2_2") (pintype "passive"))
      (node (ref "R19") (pin "1") (pinfunction "1_1") (pintype "passive"))
    )
    (net (code "27") (name "Net-(C26-Pad2)") (class "Default")
      (node (ref "C26") (pin "2") (pinfunction "2_2") (pintype "passive"))
      (node (ref "CONTOUR") (pin "3") (pinfunction "3_3") (pintype "passive"))
    )
    (net (code "28") (name "Net-(C27-Pad1)") (class "Default")
      (node (ref "C27") (pin "1") (pinfunction "1_1") (pintype "passive"))
      (node (ref "C28") (pin "+") (pinfunction "+_+") (pintype "passive"))
      (node (ref "R19") (pin "2") (pinfunction "2_2") (pintype "passive"))
    )
    (net (code "29") (name "Net-(C28-Pad-)") (class "Default")
      (node (ref "C28") (pin "-") (pinfunction "-_-") (pintype "passive"))
      (node (ref "R20") (pin "1") (pinfunction "1_1") (pintype "passive"))
    )
    (net (code "30") (name "Net-(C32-Pad+)") (class "Default")
      (node (ref "C32") (pin "+") (pinfunction "+_+") (pintype "passive"))
      (node (ref "VOL") (pin "2") (pinfunction "2_2") (pintype "passive"))
    )
    (net (code "31") (name "Net-(CLIPA-1)") (class "Default")
      (node (ref "C19") (pin "2") (pinfunction "2_2") (pintype "passive"))
      (node (ref "CLIP") (pin "A1") (pinfunction "1_A1") (pintype "passive"))
      (node (ref "D3") (pin "P$1") (pinfunction "C_P$1") (pintype "passive"))
      (node (ref "D4") (pin "ANODE") (pinfunction "A_ANODE") (pintype "passive"))
    )
    (net (code "32") (name "Net-(CLIPA-3)") (class "Default")
      (node (ref "CLIP") (pin "A3") (pinfunction "3_A3") (pintype "passive"))
      (node (ref "D5") (pin "A") (pinfunction "A_A") (pintype "passive"))
      (node (ref "D6") (pin "C") (pinfunction "C_C") (pintype "passive"))
    )
    (net (code "33") (name "Net-(D3-A)") (class "Default")
      (node (ref "C19") (pin "1") (pinfunction "1_1") (pintype "passive"))
      (node (ref "C20") (pin "2") (pinfunction "2_2") (pintype "passive"))
      (node (ref "D3") (pin "ANODE") (pinfunction "A_ANODE") (pintype "passive"))
      (node (ref "D4") (pin "P$1") (pinfunction "C_P$1") (pintype "passive"))
      (node (ref "D5") (pin "C") (pinfunction "C_C") (pintype "passive"))
      (node (ref "D6") (pin "A") (pinfunction "A_A") (pintype "passive"))
      (node (ref "R12") (pin "2") (pinfunction "2_2") (pintype "passive"))
      (node (ref "R13") (pin "2") (pinfunction "2_2") (pintype "passive"))
    )
    (net (code "34") (name "Net-(HIGHA-1)") (class "Default")
      (node (ref "C30") (pin "2") (pinfunction "2_2") (pintype "passive"))
      (node (ref "HIGH") (pin "A1") (pinfunction "1_A1") (pintype "passive"))
    )
    (net (code "35") (name "Net-(HIGHA-2)") (class "Default")
      (node (ref "C29") (pin "2") (pinfunction "2_2") (pintype "passive"))
      (node (ref "HIGH") (pin "A2") (pinfunction "2_A2") (pintype "passive"))
      (node (ref "IC2") (pin "6") (pinfunction "-IN_6") (pintype "input"))
      (node (ref "R20") (pin "2") (pinfunction "2_2") (pintype "passive"))
      (node (ref "R21") (pin "1") (pinfunction "1_1") (pintype "passive"))
    )
    (net (code "36") (name "Net-(HIGHA-3)") (class "Default")
      (node (ref "C31") (pin "2") (pinfunction "2_2") (pintype "passive"))
      (node (ref "HIGH") (pin "A3") (pinfunction "3_A3") (pintype "passive"))
    )
    (net (code "37") (name "Net-(IC1A--IN)") (class "Default")
      (node (ref "C17") (pin "2") (pinfunction "2_2") (pintype "passive"))
      (node (ref "IC1") (pin "2") (pinfunction "-IN_2") (pintype "input"))
      (node (ref "R10") (pin "2") (pinfunction "2_2") (pintype "passive"))
      (node (ref "R11") (pin "1") (pinfunction "1_1") (pintype "passive"))
    )
    (net (code "38") (name "Net-(IC1A-OUT)") (class "Default")
      (node (ref "C17") (pin "1") (pinfunction "1_1") (pintype "passive"))
      (node (ref "C18") (pin "2") (pinfunction "2_2") (pintype "passive"))
      (node (ref "IC1") (pin "1") (pinfunction "OUT_1") (pintype "output"))
      (node (ref "R11") (pin "2") (pinfunction "2_2") (pintype "passive"))
    )
    (net (code "39") (name "Net-(IC1B-+IN)") (class "Default")
      (node (ref "C13") (pin "1") (pinfunction "1_1") (pintype "passive"))
      (node (ref "IC1") (pin "5") (pinfunction "+IN_5") (pintype "input"))
      (node (ref "R8") (pin "1") (pinfunction "1_1") (pintype "passive"))
    )
    (net (code "40") (name "Net-(IC1B--IN)") (class "Default")
      (node (ref "C14") (pin "2") (pinfunction "2_2") (pintype "passive"))
      (node (ref "GAIN") (pin "1") (pinfunction "1_1") (pintype "passive"))
      (node (ref "IC1") (pin "6") (pinfunction "-IN_6") (pintype "input"))
      (node (ref "R9") (pin "2") (pinfunction "2_2") (pintype "passive"))
    )
    (net (code "41") (name "Net-(IC1B-OUT)") (class "Default")
      (node (ref "C14") (pin "1") (pinfunction "1_1") (pintype "passive"))
      (node (ref "GAIN") (pin "2") (pinfunction "2_2") (pintype "passive"))
      (node (ref "IC1") (pin "7") (pinfunction "OUT_7") (pintype "output"))
    )
    (net (code "42") (name "Net-(IC2A-+IN)") (class "Default")
      (node (ref "IC2") (pin "3") (pinfunction "+IN_3") (pintype "input"))
      (node (ref "TREBLE") (pin "2") (pinfunction "2_2") (pintype "passive"))
    )
    (net (code "43") (name "Net-(IC2A--IN)") (class "Default")
      (node (ref "C23") (pin "2") (pinfunction "2_2") (pintype "passive"))
      (node (ref "IC2") (pin "2") (pinfunction "-IN_2") (pintype "input"))
      (node (ref "R15") (pin "1") (pinfunction "1_1") (pintype "passive"))
      (node (ref "R16") (pin "1") (pinfunction "1_1") (pintype "passive"))
    )
    (net (code "44") (name "Net-(IC2A-OUT)") (class "Default")
      (node (ref "C23") (pin "1") (pinfunction "1_1") (pintype "passive"))
      (node (ref "IC2") (pin "1") (pinfunction "OUT_1") (pintype "output"))
      (node (ref "R15") (pin "2") (pinfunction "2_2") (pintype "passive"))
      (node (ref "R17") (pin "1") (pinfunction "1_1") (pintype "passive"))
    )
    (net (code "45") (name "Net-(IC2B-OUT)") (class "Default")
      (node (ref "C29") (pin "1") (pinfunction "1_1") (pintype "passive"))
      (node (ref "C30") (pin "1") (pinfunction "1_1") (pintype "passive"))
      (node (ref "C31") (pin "1") (pinfunction "1_1") (pintype "passive"))
      (node (ref "IC2") (pin "7") (pinfunction "OUT_7") (pintype "output"))
      (node (ref "R21") (pin "2") (pinfunction "2_2") (pintype "passive"))
      (node (ref "VOL") (pin "3") (pinfunction "3_3") (pintype "passive"))
    )
    (net (code "46") (name "Net-(K1A-+)") (class "Default")
      (node (ref "C12") (pin "1") (pinfunction "1_1") (pintype "passive"))
      (node (ref "D2") (pin "1") (pinfunction "1_1") (pintype "passive"))
      (node (ref "K1") (pin "1") (pinfunction "+_1") (pintype "passive"))
      (node (ref "REG2") (pin "1") (pinfunction "OUTPUT_1") (pintype "power_in"))
    )
    (net (code "47") (name "Net-(K1A--)") (class "Default")
      (node (ref "D2") (pin "2") (pinfunction "2_2") (pintype "passive"))
      (node (ref "K1") (pin "8") (pinfunction "-_8") (pintype "passive"))
      (node (ref "Q1") (pin "3") (pinfunction "C_3") (pintype "passive"))
    )
    (net (code "48") (name "Net-(K1B-O)") (class "Default")
      (node (ref "K1") (pin "2") (pinfunction "O_2") (pintype "passive"))
      (node (ref "K1") (pin "7") (pinfunction "O_7") (pintype "passive"))
    )
    (net (code "49") (name "Net-(K2-A)") (class "Default")
      (node (ref "K2") (pin "1") (pinfunction "A_1") (pintype "passive"))
      (node (ref "R6") (pin "2") (pinfunction "2_2") (pintype "passive"))
    )
    (net (code "50") (name "Net-(LEDB-S)") (class "Default")
      (node (ref "BRIGHT") (pin "2") (pinfunction "2_2") (pintype "passive"))
      (node (ref "BRIGHT") (pin "3") (pinfunction "3_3") (pintype "passive"))
      (node (ref "LED") (pin "1") (pinfunction "S_1") (pintype "passive"))
    )
    (net (code "51") (name "Net-(Q1-B)") (class "Default")
      (node (ref "Q1") (pin "1") (pinfunction "B_1") (pintype "passive"))
      (node (ref "R5") (pin "2") (pinfunction "2_2") (pintype "passive"))
    )
    (net (code "52") (name "Vb") (class "Default")
      (node (ref "C24") (pin "1") (pinfunction "1_1") (pintype "passive"))
      (node (ref "C3") (pin "+") (pinfunction "+_+") (pintype "passive"))
      (node (ref "CLIP") (pin "A2") (pinfunction "2_A2") (pintype "passive"))
      (node (ref "CONTOUR") (pin "2") (pinfunction "2_2") (pintype "passive"))
      (node (ref "IC1") (pin "3") (pinfunction "+IN_3") (pintype "input"))
      (node (ref "IC2") (pin "5") (pinfunction "+IN_5") (pintype "input"))
      (node (ref "R14") (pin "1") (pinfunction "1_1") (pintype "passive"))
      (node (ref "R2") (pin "2") (pinfunction "2_2") (pintype "passive"))
      (node (ref "R3") (pin "2") (pinfunction "2_2") (pintype "passive"))
      (node (ref "R8") (pin "2") (pinfunction "2_2") (pintype "passive"))
      (node (ref "VOL") (pin "1") (pinfunction "1_1") (pintype "passive"))
    )
    (net (code "53") (name "Vr") (class "Default")
      (node (ref "C2") (pin "+") (pinfunction "+_+") (pintype "passive"))
      (node (ref "C4") (pin "1") (pinfunction "1_1") (pintype "passive"))
      (node (ref "C5") (pin "1") (pinfunction "1_1") (pintype "passive"))
      (node (ref "IC1") (pin "8") (pinfunction "V+_8") (pintype "power_in"))
      (node (ref "IC2") (pin "8") (pinfunction "V+_8") (pintype "power_in"))
      (node (ref "R1") (pin "2") (pinfunction "2_2") (pintype "passive"))
      (node (ref "R2") (pin "1") (pinfunction "1_1") (pintype "passive"))
    )
    (net (code "54") (name "unconnected-(INPUT-PadR)") (class "Default")
      (node (ref "INPUT") (pin "R") (pinfunction "R_R") (pintype "passive+no_connect"))
    )
    (net (code "55") (name "unconnected-(OUTPUT-PadR)") (class "Default")
      (node (ref "OUTPUT") (pin "R") (pinfunction "R_R") (pintype "passive+no_connect"))
    )
  )
)
